# Main.net
KiCad netlist of a schematic drawn in Altium Designer
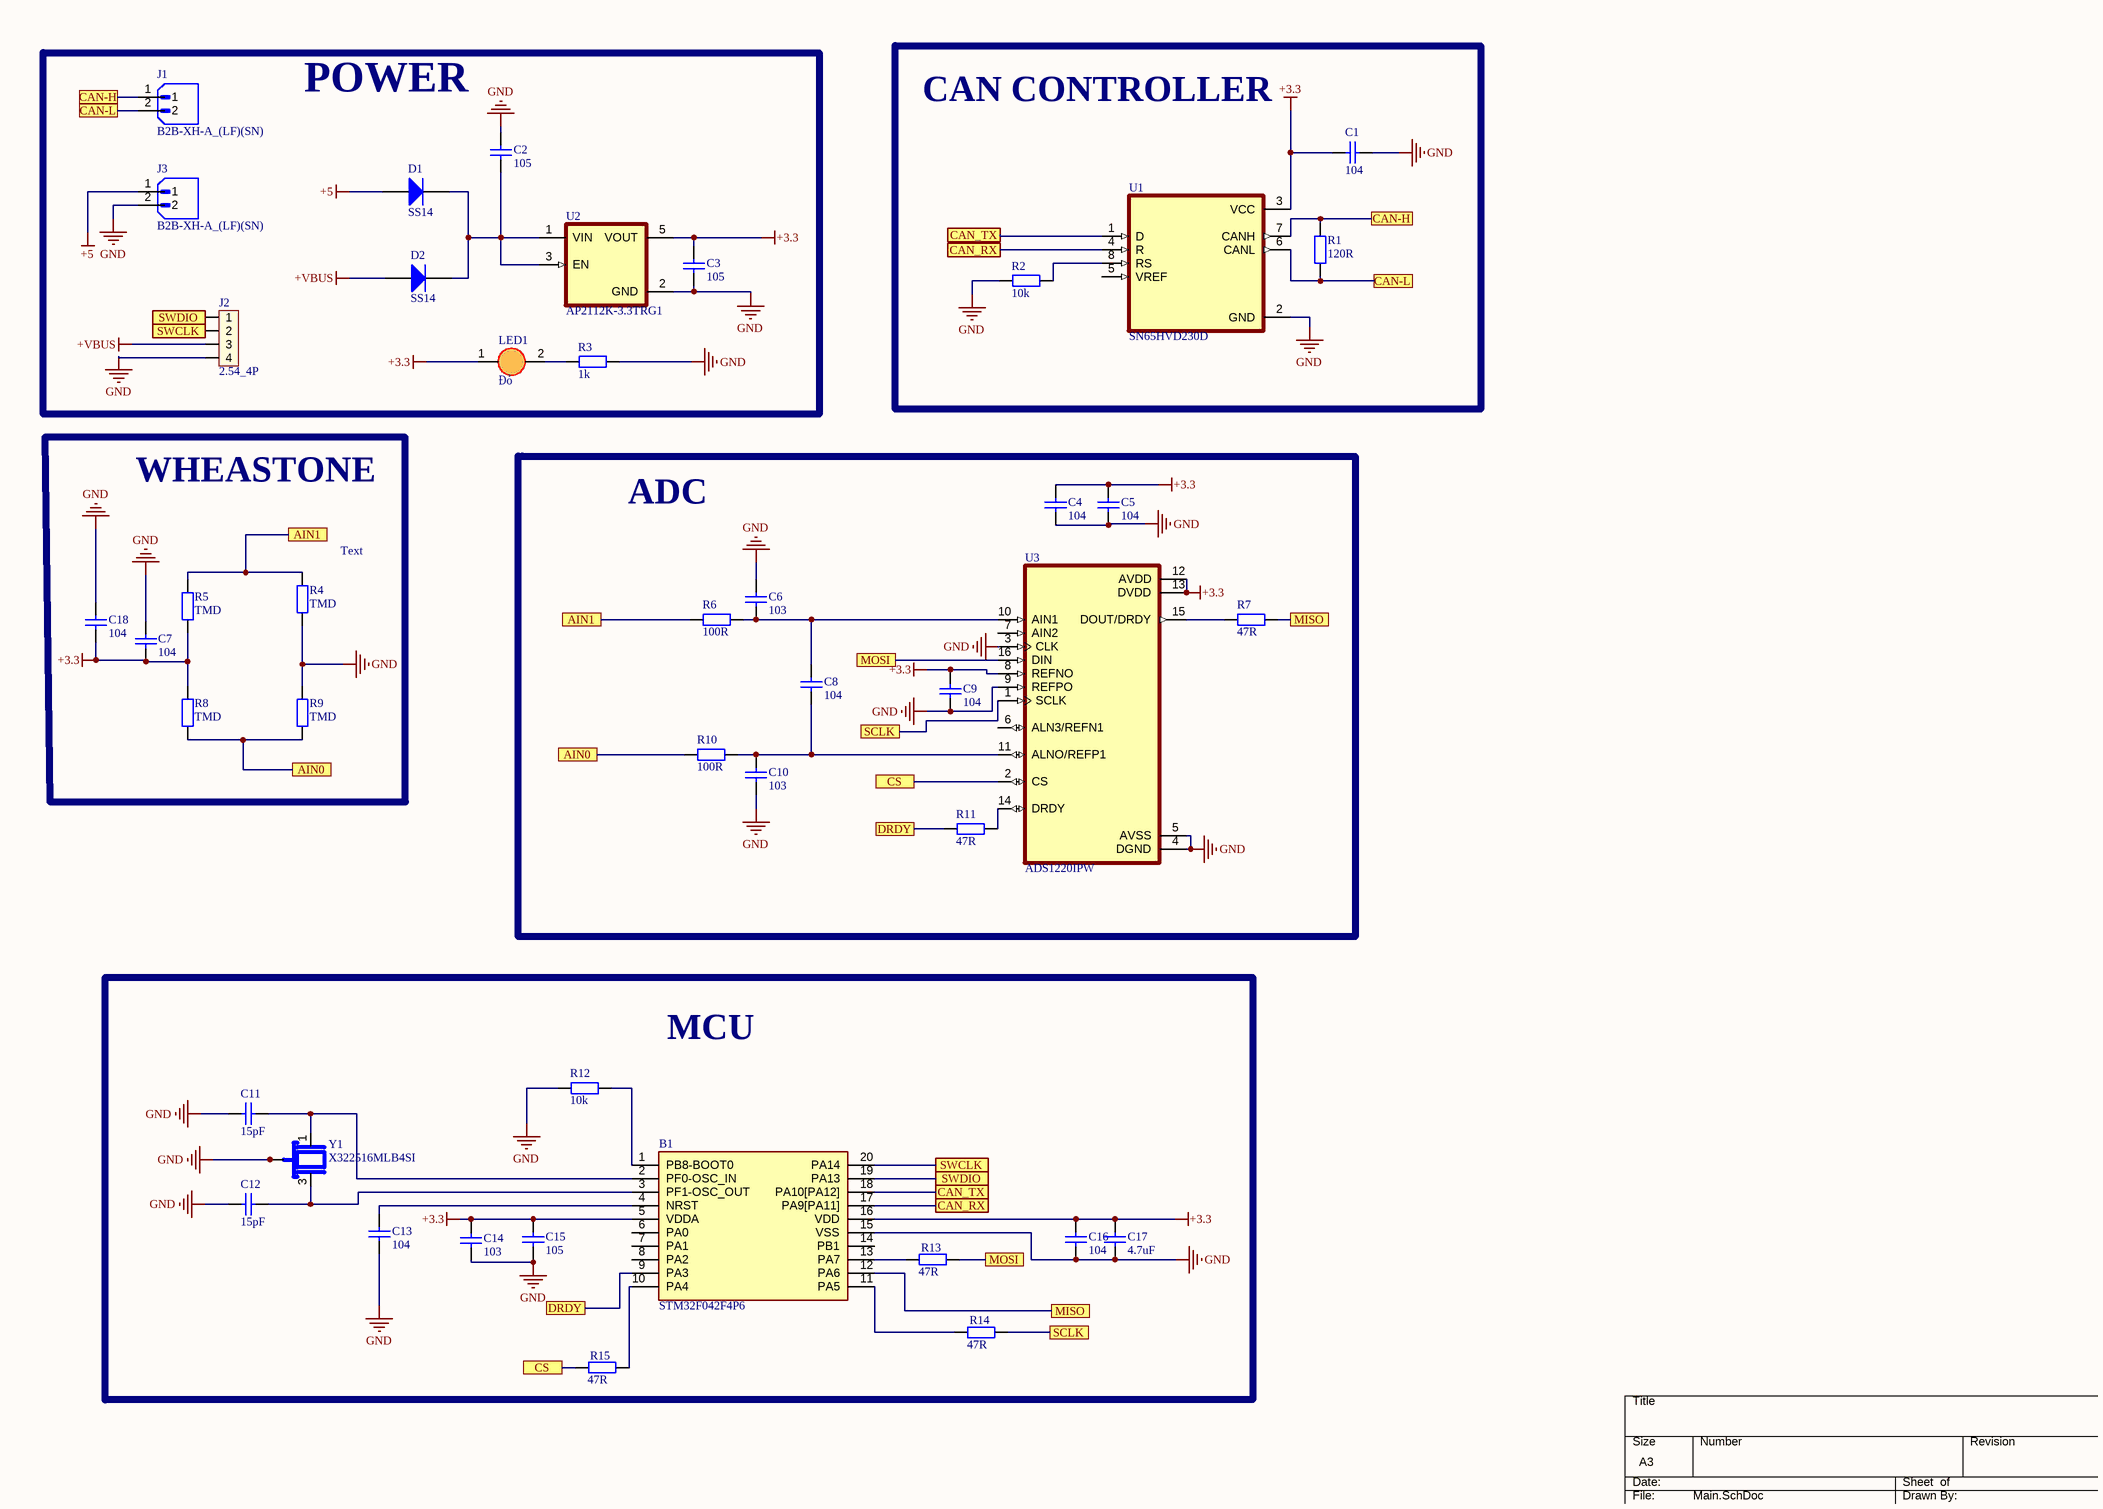
[diagram p0: Main.SchDoc]

(export (version "E")
  (design (tool "Eeschema 10.0.6"))
  (components
    (comp (ref "B1")
      (value "STM32F042F4P6")
      (footprint "SOP65P640X120-20N")
      (fields (field (name "MOUSER PART NUMBER") "511-STM32F042F4P6"))
      (libsource (lib "STM32F042F4P6") (part "STM32F042F4P6"))
    )
    (comp (ref "C1")
      (value "104")
      (footprint "tu 0603")
      (description "Dán")
      (libsource (lib "THU VIEN SCH") (part "Tu 0603 104 50V 10%"))
    )
    (comp (ref "C2")
      (value "105")
      (footprint "tu 0603")
      (description "Dán")
      (libsource (lib "THU VIEN SCH") (part "Tu 0603 105 16V 20%"))
    )
    (comp (ref "C3")
      (value "105")
      (footprint "tu 0603")
      (description "Dán")
      (libsource (lib "THU VIEN SCH") (part "Tu 0603 105 16V 20%"))
    )
    (comp (ref "C4")
      (value "104")
      (footprint "tu 0603")
      (description "Dán")
      (libsource (lib "THU VIEN SCH") (part "Tu 0603 104 50V 10%"))
    )
    (comp (ref "C5")
      (value "104")
      (footprint "tu 0603")
      (description "Dán")
      (libsource (lib "THU VIEN SCH") (part "Tu 0603 104 50V 10%"))
    )
    (comp (ref "C6")
      (value "103")
      (footprint "tu 0603")
      (description "Dán")
      (libsource (lib "THU VIEN SCH") (part "Tu 0603 103 50V 10%"))
    )
    (comp (ref "C7")
      (value "104")
      (footprint "tu 0603")
      (description "Dán")
      (libsource (lib "THU VIEN SCH") (part "Tu 0603 104 50V 10%"))
    )
    (comp (ref "C8")
      (value "104")
      (footprint "tu 0603")
      (description "Dán")
      (libsource (lib "THU VIEN SCH") (part "Tu 0603 104 50V 10%"))
    )
    (comp (ref "C9")
      (value "104")
      (footprint "tu 0603")
      (description "Dán")
      (libsource (lib "THU VIEN SCH") (part "Tu 0603 104 50V 10%"))
    )
    (comp (ref "C10")
      (value "103")
      (footprint "tu 0603")
      (description "Dán")
      (libsource (lib "THU VIEN SCH") (part "Tu 0603 103 50V 10%"))
    )
    (comp (ref "C11")
      (value "15pF")
      (footprint "tu 0603")
      (description "Dán")
      (libsource (lib "THU VIEN SCH") (part "Tu 0603 104 50V 10%"))
    )
    (comp (ref "C12")
      (value "15pF")
      (footprint "tu 0603")
      (description "Dán")
      (libsource (lib "THU VIEN SCH") (part "Tu 0603 104 50V 10%"))
    )
    (comp (ref "C13")
      (value "104")
      (footprint "tu 0603")
      (description "Dán")
      (libsource (lib "THU VIEN SCH") (part "Tu 0603 104 50V 10%"))
    )
    (comp (ref "C14")
      (value "103")
      (footprint "tu 0603")
      (description "Dán")
      (libsource (lib "THU VIEN SCH") (part "Tu 0603 103 50V 10%"))
    )
    (comp (ref "C15")
      (value "105")
      (footprint "tu 0603")
      (description "Dán")
      (libsource (lib "THU VIEN SCH") (part "Tu 0603 105 16V 20%"))
    )
    (comp (ref "C16")
      (value "104")
      (footprint "tu 0603")
      (description "Dán")
      (libsource (lib "THU VIEN SCH") (part "Tu 0603 104 50V 10%"))
    )
    (comp (ref "C17")
      (value "4.7uF")
      (footprint "tu 0805")
      (description "Dán")
      (libsource (lib "THU VIEN SCH") (part "Tu 0805 475 25V 20%"))
    )
    (comp (ref "C18")
      (value "104")
      (footprint "tu 0603")
      (description "Dán")
      (libsource (lib "THU VIEN SCH") (part "Tu 0603 104 50V 10%"))
    )
    (comp (ref "D1")
      (value "SS14")
      (footprint "DIODE SMD")
      (description "Dán")
      (libsource (lib "THU VIEN SCH") (part "Diode SS14 ( 1N5819)"))
    )
    (comp (ref "D2")
      (value "SS14")
      (footprint "DIODE SMD")
      (description "Dán")
      (libsource (lib "THU VIEN SCH") (part "Diode SS14 ( 1N5819)"))
    )
    (comp (ref "J1")
      (value "B2B-XH-A_(LF)(SN)")
      (footprint "JST_B2B-XH-A_(LF)(SN)")
      (description "Connector Header Through Hole 2 position 0.098 (2.50mm)")
      (fields (field (name "MF") "JST Sales") (field (name "MP") "B2B-XH-A (LF)(SN)"))
      (libsource (lib "B2B-XH-A__LF__SN_") (part "B2B-XH-A_(LF)(SN)"))
    )
    (comp (ref "J2")
      (value "2.54_4P")
      (footprint "JP4")
      (description "Cắm st link cho stm32")
      (libsource (lib "THU VIEN SCH") (part "Jum Don Duc 2.54_4P"))
    )
    (comp (ref "J3")
      (value "B2B-XH-A_(LF)(SN)")
      (footprint "JST_B2B-XH-A_(LF)(SN)")
      (description "Connector Header Through Hole 2 position 0.098 (2.50mm)")
      (fields (field (name "MF") "JST Sales") (field (name "MP") "B2B-XH-A (LF)(SN)"))
      (libsource (lib "B2B-XH-A__LF__SN_") (part "B2B-XH-A_(LF)(SN)"))
    )
    (comp (ref "LED1")
      (value "Đỏ")
      (footprint "led 0805")
      (description "Dán")
      (libsource (lib "THU VIEN SCH") (part "LED 0805"))
    )
    (comp (ref "R1")
      (value "120R")
      (footprint "tro smd 0603")
      (description "Dán")
      (libsource (lib "THU VIEN SCH") (part "Tro 0603 5% 100R"))
    )
    (comp (ref "R2")
      (value "10k")
      (footprint "tro smd 0603")
      (description "Dán")
      (libsource (lib "THU VIEN SCH") (part "Tro 0603 1% 10k"))
    )
    (comp (ref "R3")
      (value "1k")
      (footprint "tro smd 0603")
      (description "Dán")
      (libsource (lib "THU VIEN SCH") (part "Tro 0603 1% 1k"))
    )
    (comp (ref "R4")
      (value "TMD")
      (footprint "tro smd 1206")
      (description "Dán")
      (libsource (lib "THU VIEN SCH") (part "Tro 1206 1% 1k"))
    )
    (comp (ref "R5")
      (value "TMD")
      (footprint "tro smd 1206")
      (description "Dán")
      (libsource (lib "THU VIEN SCH") (part "Tro 1206 1% 1k"))
    )
    (comp (ref "R6")
      (value "100R")
      (footprint "tro smd 0603")
      (description "Dán")
      (libsource (lib "THU VIEN SCH") (part "Tro 0603 5% 100R"))
    )
    (comp (ref "R7")
      (value "47R")
      (footprint "tro smd 0603")
      (description "Dán")
      (libsource (lib "THU VIEN SCH") (part "Tro 0603 1% 56R"))
    )
    (comp (ref "R8")
      (value "TMD")
      (footprint "tro smd 1206")
      (description "Dán")
      (libsource (lib "THU VIEN SCH") (part "Tro 1206 1% 1k"))
    )
    (comp (ref "R9")
      (value "TMD")
      (footprint "tro smd 1206")
      (description "Dán")
      (libsource (lib "THU VIEN SCH") (part "Tro 1206 1% 1k"))
    )
    (comp (ref "R10")
      (value "100R")
      (footprint "tro smd 0603")
      (description "Dán")
      (libsource (lib "THU VIEN SCH") (part "Tro 0603 5% 100R"))
    )
    (comp (ref "R11")
      (value "47R")
      (footprint "tro smd 0603")
      (description "Dán")
      (libsource (lib "THU VIEN SCH") (part "Tro 0603 1% 56R"))
    )
    (comp (ref "R12")
      (value "10k")
      (footprint "tro smd 0603")
      (description "Dán")
      (libsource (lib "THU VIEN SCH") (part "Tro 0603 1% 10k"))
    )
    (comp (ref "R13")
      (value "47R")
      (footprint "tro smd 0603")
      (description "Dán")
      (libsource (lib "THU VIEN SCH") (part "Tro 0603 1% 56R"))
    )
    (comp (ref "R14")
      (value "47R")
      (footprint "tro smd 0603")
      (description "Dán")
      (libsource (lib "THU VIEN SCH") (part "Tro 0603 1% 56R"))
    )
    (comp (ref "R15")
      (value "47R")
      (footprint "tro smd 0603")
      (description "Dán")
      (libsource (lib "THU VIEN SCH") (part "Tro 0603 1% 56R"))
    )
    (comp (ref "U1")
      (value "SN65HVD230D")
      (footprint "SOIC127P599X175-8N")
      (description "3.3 V CAN Transceiver with Standby Mode")
      (fields (field (name "MF") "Texas Instruments"))
      (libsource (lib "SN65HVD230D") (part "SN65HVD230D"))
    )
    (comp (ref "U2")
      (value "AP2112K-3.3TRG1")
      (footprint "SOT95P285X140-5N")
      (description "Linear Voltage Regulator IC Positive Fixed 1 Output 600mA SOT-25")
      (fields (field (name "MF") "Diodes Inc."))
      (libsource (lib "AP2112K-3.3TRG1") (part "AP2112K-3.3TRG1"))
    )
    (comp (ref "U3")
      (value "ADS1220IPW")
      (footprint "SOP65P640X120-16N")
      (description "24-bit, 2-kSPS, four-channel, low-power, delta-sigma ADC with PGA, VREF, SPI and two IDACs")
      (fields (field (name "MF") "Texas Instruments"))
      (libsource (lib "ADS1220IPW") (part "ADS1220IPW"))
    )
    (comp (ref "Y1")
      (value "X322516MLB4SI")
      (footprint "OSC_X322516MLB4SI")
      (description "External dimensions: 3.2 x 2.5 x 0.8 mm.Frequency range: 11.0592MHz ~54MHz")
      (fields (field (name "MF") "YXC"))
      (libsource (lib "X322516MLB4SI") (part "X322516MLB4SI"))
    )
  )
  (nets
    (net (code "1") (name "+3.3") (class "Default")
      (node (ref "B1") (pin "16") (pinfunction "VDD_16") (pintype "passive"))
      (node (ref "B1") (pin "5") (pinfunction "VDDA_5") (pintype "passive"))
      (node (ref "C1") (pin "1") (pinfunction "1_1") (pintype "passive"))
      (node (ref "C14") (pin "1") (pinfunction "1_1") (pintype "passive"))
      (node (ref "C15") (pin "2") (pinfunction "2_2") (pintype "passive"))
      (node (ref "C16") (pin "1") (pinfunction "1_1") (pintype "passive"))
      (node (ref "C17") (pin "1") (pinfunction "1_1") (pintype "passive"))
      (node (ref "C18") (pin "2") (pinfunction "2_2") (pintype "passive"))
      (node (ref "C3") (pin "2") (pinfunction "2_2") (pintype "passive"))
      (node (ref "C4") (pin "1") (pinfunction "1_1") (pintype "passive"))
      (node (ref "C5") (pin "1") (pinfunction "1_1") (pintype "passive"))
      (node (ref "C7") (pin "2") (pinfunction "2_2") (pintype "passive"))
      (node (ref "C9") (pin "1") (pinfunction "1_1") (pintype "passive"))
      (node (ref "LED1") (pin "1") (pinfunction "A_1") (pintype "passive"))
      (node (ref "R5") (pin "1") (pinfunction "1_1") (pintype "passive"))
      (node (ref "R8") (pin "2") (pinfunction "2_2") (pintype "passive"))
      (node (ref "U1") (pin "3") (pinfunction "VCC_3") (pintype "power_in"))
      (node (ref "U2") (pin "5") (pinfunction "VOUT_5") (pintype "power_in"))
      (node (ref "U3") (pin "12") (pinfunction "AVDD_12") (pintype "power_in"))
      (node (ref "U3") (pin "13") (pinfunction "DVDD_13") (pintype "power_in"))
      (node (ref "U3") (pin "8") (pinfunction "REFNO_8") (pintype "input"))
    )
    (net (code "2") (name "+5") (class "Default")
      (node (ref "D1") (pin "1") (pinfunction "A_1") (pintype "passive"))
      (node (ref "J3") (pin "1") (pinfunction "1_1") (pintype "passive"))
    )
    (net (code "3") (name "+VBUS") (class "Default")
      (node (ref "D2") (pin "1") (pinfunction "A_1") (pintype "passive"))
      (node (ref "J2") (pin "3") (pinfunction "3_3") (pintype "passive"))
    )
    (net (code "4") (name "/AIN0") (class "Default")
      (node (ref "R10") (pin "1") (pinfunction "1_1") (pintype "passive"))
      (node (ref "R8") (pin "1") (pinfunction "1_1") (pintype "passive"))
      (node (ref "R9") (pin "2") (pinfunction "2_2") (pintype "passive"))
    )
    (net (code "5") (name "/AIN1") (class "Default")
      (node (ref "R4") (pin "2") (pinfunction "2_2") (pintype "passive"))
      (node (ref "R5") (pin "2") (pinfunction "2_2") (pintype "passive"))
      (node (ref "R6") (pin "1") (pinfunction "1_1") (pintype "passive"))
    )
    (net (code "6") (name "/CAN-H") (class "Default")
      (node (ref "J1") (pin "1") (pinfunction "1_1") (pintype "passive"))
      (node (ref "R1") (pin "2") (pinfunction "2_2") (pintype "passive"))
      (node (ref "U1") (pin "7") (pinfunction "CANH_7") (pintype "output"))
    )
    (net (code "7") (name "/CAN-L") (class "Default")
      (node (ref "J1") (pin "2") (pinfunction "2_2") (pintype "passive"))
      (node (ref "R1") (pin "1") (pinfunction "1_1") (pintype "passive"))
      (node (ref "U1") (pin "6") (pinfunction "CANL_6") (pintype "output"))
    )
    (net (code "8") (name "/CAN_RX") (class "Default")
      (node (ref "B1") (pin "17") (pinfunction "PA9[PA11]_17") (pintype "passive"))
      (node (ref "U1") (pin "4") (pinfunction "R_4") (pintype "input"))
    )
    (net (code "9") (name "/CAN_TX") (class "Default")
      (node (ref "B1") (pin "18") (pinfunction "PA10[PA12]_18") (pintype "passive"))
      (node (ref "U1") (pin "1") (pinfunction "D_1") (pintype "input"))
    )
    (net (code "10") (name "/CS") (class "Default")
      (node (ref "R15") (pin "1") (pinfunction "1_1") (pintype "passive"))
      (node (ref "U3") (pin "2") (pinfunction "CS_2") (pintype "bidirectional"))
    )
    (net (code "11") (name "/DRDY") (class "Default")
      (node (ref "B1") (pin "9") (pinfunction "PA3_9") (pintype "passive"))
      (node (ref "R11") (pin "1") (pinfunction "1_1") (pintype "passive"))
    )
    (net (code "12") (name "/MISO") (class "Default")
      (node (ref "B1") (pin "12") (pinfunction "PA6_12") (pintype "passive"))
      (node (ref "R7") (pin "2") (pinfunction "2_2") (pintype "passive"))
    )
    (net (code "13") (name "/MOSI") (class "Default")
      (node (ref "R13") (pin "2") (pinfunction "2_2") (pintype "passive"))
      (node (ref "U3") (pin "16") (pinfunction "DIN_16") (pintype "input"))
    )
    (net (code "14") (name "/SCLK") (class "Default")
      (node (ref "R14") (pin "2") (pinfunction "2_2") (pintype "passive"))
      (node (ref "U3") (pin "1") (pinfunction "SCLK_1") (pintype "input"))
    )
    (net (code "15") (name "/SWCLK") (class "Default")
      (node (ref "B1") (pin "20") (pinfunction "PA14_20") (pintype "passive"))
      (node (ref "J2") (pin "2") (pinfunction "2_2") (pintype "passive"))
    )
    (net (code "16") (name "/SWDIO") (class "Default")
      (node (ref "B1") (pin "19") (pinfunction "PA13_19") (pintype "passive"))
      (node (ref "J2") (pin "1") (pinfunction "1_1") (pintype "passive"))
    )
    (net (code "17") (name "GND") (class "Default")
      (node (ref "B1") (pin "15") (pinfunction "VSS_15") (pintype "passive"))
      (node (ref "C1") (pin "2") (pinfunction "2_2") (pintype "passive"))
      (node (ref "C10") (pin "2") (pinfunction "2_2") (pintype "passive"))
      (node (ref "C11") (pin "1") (pinfunction "1_1") (pintype "passive"))
      (node (ref "C12") (pin "1") (pinfunction "1_1") (pintype "passive"))
      (node (ref "C13") (pin "2") (pinfunction "2_2") (pintype "passive"))
      (node (ref "C14") (pin "2") (pinfunction "2_2") (pintype "passive"))
      (node (ref "C15") (pin "1") (pinfunction "1_1") (pintype "passive"))
      (node (ref "C16") (pin "2") (pinfunction "2_2") (pintype "passive"))
      (node (ref "C17") (pin "2") (pinfunction "2_2") (pintype "passive"))
      (node (ref "C18") (pin "1") (pinfunction "1_1") (pintype "passive"))
      (node (ref "C2") (pin "1") (pinfunction "1_1") (pintype "passive"))
      (node (ref "C3") (pin "1") (pinfunction "1_1") (pintype "passive"))
      (node (ref "C4") (pin "2") (pinfunction "2_2") (pintype "passive"))
      (node (ref "C5") (pin "2") (pinfunction "2_2") (pintype "passive"))
      (node (ref "C6") (pin "1") (pinfunction "1_1") (pintype "passive"))
      (node (ref "C7") (pin "1") (pinfunction "1_1") (pintype "passive"))
      (node (ref "C9") (pin "2") (pinfunction "2_2") (pintype "passive"))
      (node (ref "J2") (pin "4") (pinfunction "4_4") (pintype "passive"))
      (node (ref "J3") (pin "2") (pinfunction "2_2") (pintype "passive"))
      (node (ref "R12") (pin "1") (pinfunction "1_1") (pintype "passive"))
      (node (ref "R2") (pin "1") (pinfunction "1_1") (pintype "passive"))
      (node (ref "R3") (pin "2") (pinfunction "2_2") (pintype "passive"))
      (node (ref "R4") (pin "1") (pinfunction "1_1") (pintype "passive"))
      (node (ref "R9") (pin "1") (pinfunction "1_1") (pintype "passive"))
      (node (ref "U1") (pin "2") (pinfunction "GND_2") (pintype "power_in"))
      (node (ref "U2") (pin "2") (pinfunction "GND_2") (pintype "power_in"))
      (node (ref "U3") (pin "3") (pinfunction "CLK_3") (pintype "input"))
      (node (ref "U3") (pin "4") (pinfunction "DGND_4") (pintype "power_in"))
      (node (ref "U3") (pin "5") (pinfunction "AVSS_5") (pintype "power_in"))
      (node (ref "U3") (pin "9") (pinfunction "REFPO_9") (pintype "input"))
      (node (ref "Y1") (pin "2") (pinfunction "GND_2") (pintype "power_in"))
      (node (ref "Y1") (pin "4") (pinfunction "GND_4") (pintype "power_in"))
    )
    (net (code "18") (name "Net-(B1-NRST)") (class "Default")
      (node (ref "B1") (pin "4") (pinfunction "NRST_4") (pintype "passive"))
      (node (ref "C13") (pin "1") (pinfunction "1_1") (pintype "passive"))
    )
    (net (code "19") (name "Net-(B1-PA4)") (class "Default")
      (node (ref "B1") (pin "10") (pinfunction "PA4_10") (pintype "passive"))
      (node (ref "R15") (pin "2") (pinfunction "2_2") (pintype "passive"))
    )
    (net (code "20") (name "Net-(B1-PA5)") (class "Default")
      (node (ref "B1") (pin "11") (pinfunction "PA5_11") (pintype "passive"))
      (node (ref "R14") (pin "1") (pinfunction "1_1") (pintype "passive"))
    )
    (net (code "21") (name "Net-(B1-PA7)") (class "Default")
      (node (ref "B1") (pin "13") (pinfunction "PA7_13") (pintype "passive"))
      (node (ref "R13") (pin "1") (pinfunction "1_1") (pintype "passive"))
    )
    (net (code "22") (name "Net-(B1-PB8-BOOT0)") (class "Default")
      (node (ref "B1") (pin "1") (pinfunction "PB8-BOOT0_1") (pintype "passive"))
      (node (ref "R12") (pin "2") (pinfunction "2_2") (pintype "passive"))
    )
    (net (code "23") (name "Net-(B1-PF0-OSC_IN)") (class "Default")
      (node (ref "B1") (pin "2") (pinfunction "PF0-OSC_IN_2") (pintype "passive"))
      (node (ref "C11") (pin "2") (pinfunction "2_2") (pintype "passive"))
      (node (ref "Y1") (pin "1") (pinfunction "1_1") (pintype "passive"))
    )
    (net (code "24") (name "Net-(B1-PF1-OSC_OUT)") (class "Default")
      (node (ref "B1") (pin "3") (pinfunction "PF1-OSC_OUT_3") (pintype "passive"))
      (node (ref "C12") (pin "2") (pinfunction "2_2") (pintype "passive"))
      (node (ref "Y1") (pin "3") (pinfunction "3_3") (pintype "passive"))
    )
    (net (code "25") (name "Net-(D1-K)") (class "Default")
      (node (ref "C2") (pin "2") (pinfunction "2_2") (pintype "passive"))
      (node (ref "D1") (pin "2") (pinfunction "K_2") (pintype "passive"))
      (node (ref "D2") (pin "2") (pinfunction "K_2") (pintype "passive"))
      (node (ref "U2") (pin "1") (pinfunction "VIN_1") (pintype "power_in"))
      (node (ref "U2") (pin "3") (pinfunction "EN_3") (pintype "input"))
    )
    (net (code "26") (name "Net-(LED1-K)") (class "Default")
      (node (ref "LED1") (pin "2") (pinfunction "K_2") (pintype "passive"))
      (node (ref "R3") (pin "1") (pinfunction "1_1") (pintype "passive"))
    )
    (net (code "27") (name "Net-(U1-RS)") (class "Default")
      (node (ref "R2") (pin "2") (pinfunction "2_2") (pintype "passive"))
      (node (ref "U1") (pin "8") (pinfunction "RS_8") (pintype "input"))
    )
    (net (code "28") (name "Net-(U3-AIN1)") (class "Default")
      (node (ref "C6") (pin "2") (pinfunction "2_2") (pintype "passive"))
      (node (ref "C8") (pin "1") (pinfunction "1_1") (pintype "passive"))
      (node (ref "R6") (pin "2") (pinfunction "2_2") (pintype "passive"))
      (node (ref "U3") (pin "10") (pinfunction "AIN1_10") (pintype "input"))
    )
    (net (code "29") (name "Net-(U3-ALNO{slash}REFP1)") (class "Default")
      (node (ref "C10") (pin "1") (pinfunction "1_1") (pintype "passive"))
      (node (ref "C8") (pin "2") (pinfunction "2_2") (pintype "passive"))
      (node (ref "R10") (pin "2") (pinfunction "2_2") (pintype "passive"))
      (node (ref "U3") (pin "11") (pinfunction "ALNO/REFP1_11") (pintype "bidirectional"))
    )
    (net (code "30") (name "Net-(U3-DOUT{slash}DRDY)") (class "Default")
      (node (ref "R7") (pin "1") (pinfunction "1_1") (pintype "passive"))
      (node (ref "U3") (pin "15") (pinfunction "DOUT/DRDY_15") (pintype "output"))
    )
    (net (code "31") (name "Net-(U3-DRDY)") (class "Default")
      (node (ref "R11") (pin "2") (pinfunction "2_2") (pintype "passive"))
      (node (ref "U3") (pin "14") (pinfunction "DRDY_14") (pintype "bidirectional"))
    )
    (net (code "32") (name "unconnected-(B1-PA0-Pad6)") (class "Default")
      (node (ref "B1") (pin "6") (pinfunction "PA0_6") (pintype "passive"))
    )
    (net (code "33") (name "unconnected-(B1-PA1-Pad7)") (class "Default")
      (node (ref "B1") (pin "7") (pinfunction "PA1_7") (pintype "passive"))
    )
    (net (code "34") (name "unconnected-(B1-PA2-Pad8)") (class "Default")
      (node (ref "B1") (pin "8") (pinfunction "PA2_8") (pintype "passive"))
    )
    (net (code "35") (name "unconnected-(B1-PB1-Pad14)") (class "Default")
      (node (ref "B1") (pin "14") (pinfunction "PB1_14") (pintype "passive"))
    )
    (net (code "36") (name "unconnected-(U1-VREF-Pad5)") (class "Default")
      (node (ref "U1") (pin "5") (pinfunction "VREF_5") (pintype "input"))
    )
    (net (code "37") (name "unconnected-(U3-AIN2-Pad7)") (class "Default")
      (node (ref "U3") (pin "7") (pinfunction "AIN2_7") (pintype "input"))
    )
    (net (code "38") (name "unconnected-(U3-ALN3{slash}REFN1-Pad6)") (class "Default")
      (node (ref "U3") (pin "6") (pinfunction "ALN3/REFN1_6") (pintype "bidirectional"))
    )
  )
)
